# 20180608-iot.net
KiCad netlist of a schematic drawn in EAGLE
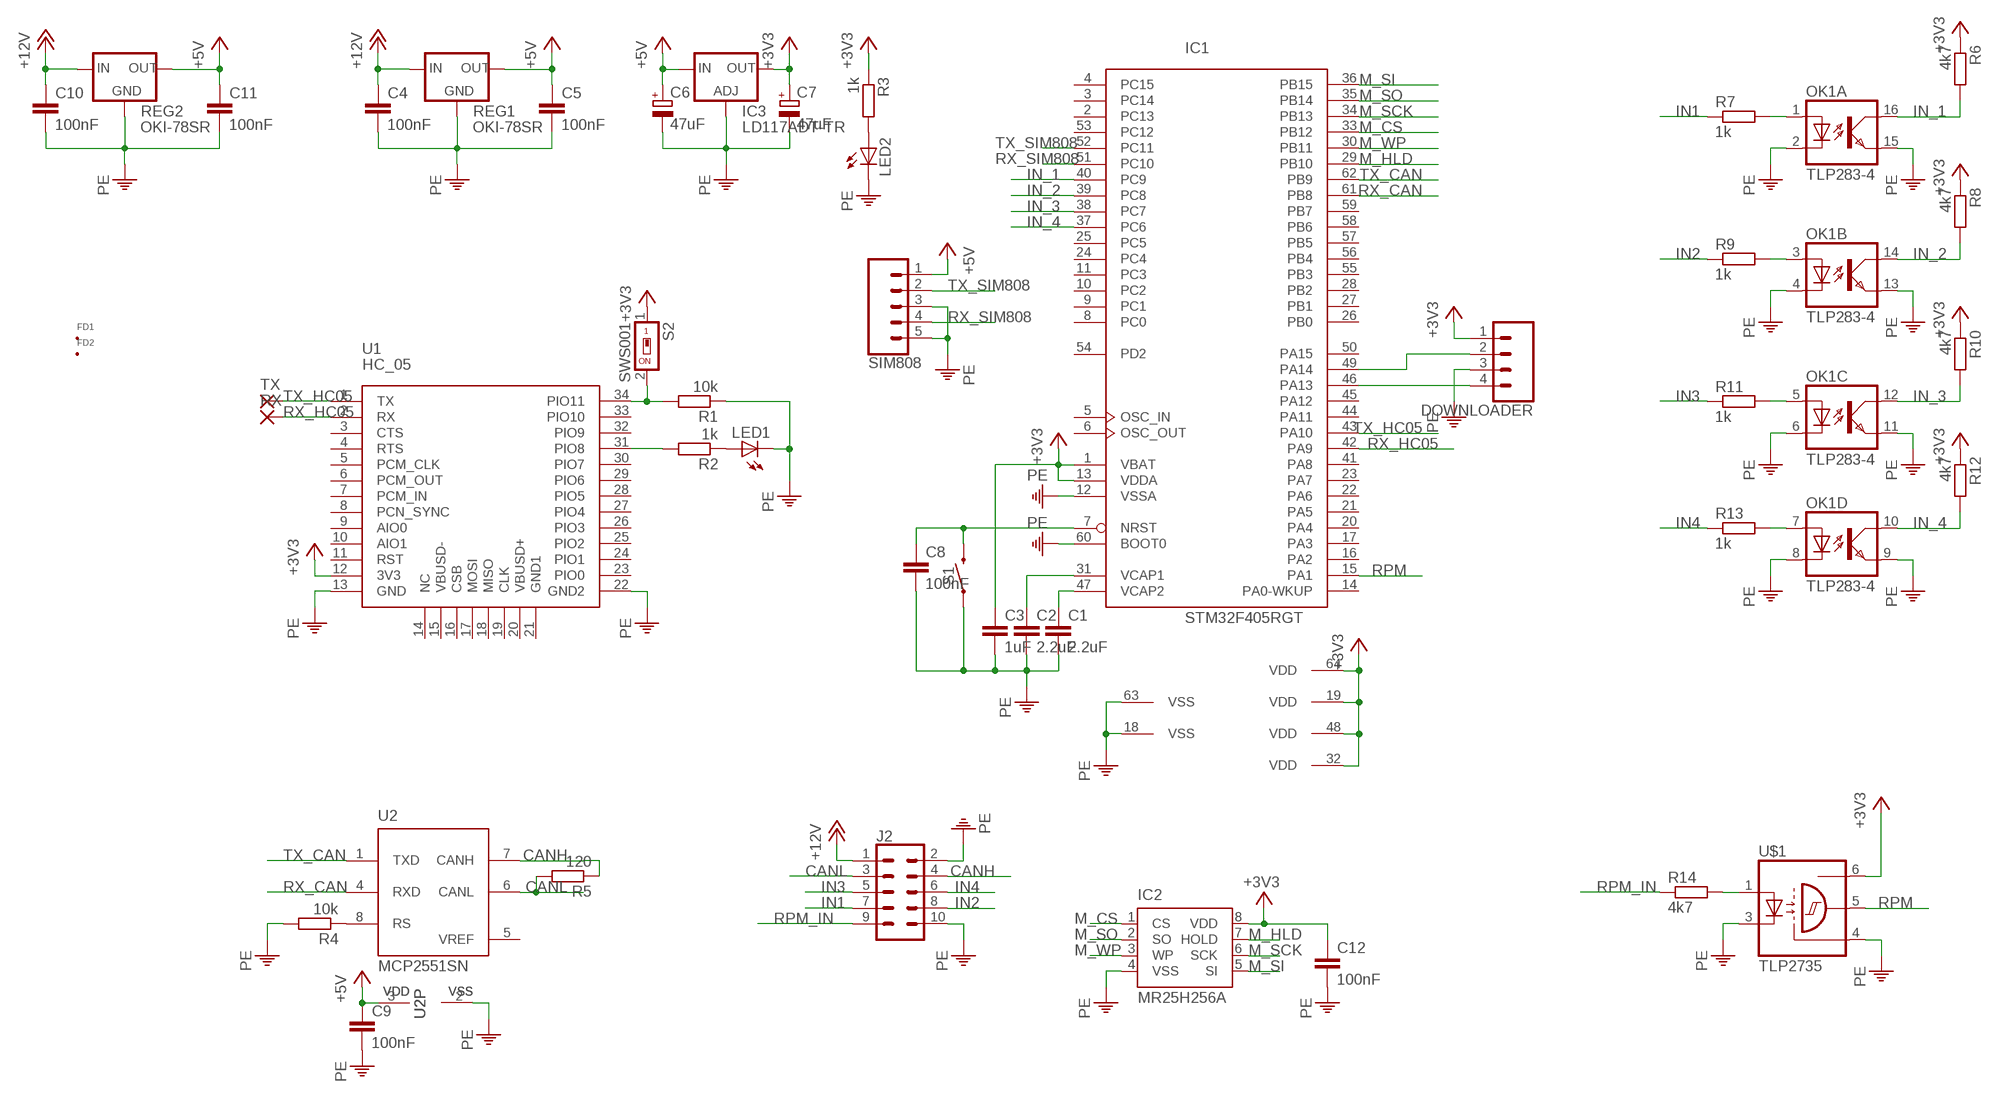
[diagram p0: schematic, sheet 1]

(export (version "E")
  (design (tool "Eeschema 10.0.6"))
  (components
    (comp (ref "C1")
      (value "2.2uF")
      (footprint "eagle-import:C0805")
      (libsource (lib "eagle-import") (part "C-EUC0805"))
    )
    (comp (ref "C2")
      (value "2.2uF")
      (footprint "eagle-import:C0805")
      (libsource (lib "eagle-import") (part "C-EUC0805"))
    )
    (comp (ref "C3")
      (value "1uF")
      (footprint "eagle-import:C0805")
      (libsource (lib "eagle-import") (part "C-EUC0805"))
    )
    (comp (ref "C4")
      (value "100nF")
      (footprint "eagle-import:C0805")
      (libsource (lib "eagle-import") (part "C-EUC0805"))
    )
    (comp (ref "C5")
      (value "100nF")
      (footprint "eagle-import:C0805")
      (libsource (lib "eagle-import") (part "C-EUC0805"))
    )
    (comp (ref "C6")
      (value "47uF")
      (footprint "eagle-import:CT7343")
      (libsource (lib "eagle-import") (part "CPOL-EUCT7343"))
    )
    (comp (ref "C7")
      (value "47uF")
      (footprint "eagle-import:CT7343")
      (libsource (lib "eagle-import") (part "CPOL-EUCT7343"))
    )
    (comp (ref "C8")
      (value "100nF")
      (footprint "eagle-import:C0805")
      (libsource (lib "eagle-import") (part "C-EUC0805"))
    )
    (comp (ref "C9")
      (value "100nF")
      (footprint "eagle-import:C0805")
      (libsource (lib "eagle-import") (part "C-EUC0805"))
    )
    (comp (ref "C10")
      (value "100nF")
      (footprint "eagle-import:C0805")
      (libsource (lib "eagle-import") (part "C-EUC0805"))
    )
    (comp (ref "C11")
      (value "100nF")
      (footprint "eagle-import:C0805")
      (libsource (lib "eagle-import") (part "C-EUC0805"))
    )
    (comp (ref "C12")
      (value "100nF")
      (footprint "eagle-import:C0805")
      (libsource (lib "eagle-import") (part "C-EUC0805"))
    )
    (comp (ref "DOWNLOADER")
      (value "CONN_04")
      (footprint "eagle-import:1X04")
      (libsource (lib "eagle-import") (part "CONN_04"))
    )
    (comp (ref "FD1")
      (value "FID_40MIL")
      (footprint "eagle-import:FID_040")
      (libsource (lib "eagle-import") (part "FID_40MIL"))
    )
    (comp (ref "FD2")
      (value "FID_40MIL")
      (footprint "eagle-import:FID_040")
      (libsource (lib "eagle-import") (part "FID_40MIL"))
    )
    (comp (ref "IC1")
      (value "STM32F405RGT")
      (footprint "eagle-import:LQFP64")
      (fields (field (name "SPICEPREFIX") "X"))
      (libsource (lib "eagle-import") (part "STM32F405RTG"))
    )
    (comp (ref "IC2")
      (value "MR25H256A")
      (footprint "eagle-import:SON127P600X500X90-9T210")
      (libsource (lib "eagle-import") (part "MR25H256A"))
    )
    (comp (ref "IC3")
      (value "LD117ADT-TR")
      (footprint "eagle-import:DPACK")
      (libsource (lib "eagle-import") (part "LD117A?DT-TR"))
    )
    (comp (ref "J2")
      (value "CONN_05X2")
      (footprint "eagle-import:2X5-EDGE_SMD")
      (libsource (lib "eagle-import") (part "CONN_05X2"))
    )
    (comp (ref "LED1")
      (value "LEDCHIP-LED0805")
      (footprint "eagle-import:CHIP-LED0805")
      (libsource (lib "eagle-import") (part "LEDCHIP-LED0805"))
    )
    (comp (ref "LED2")
      (value "LEDCHIP-LED0805")
      (footprint "eagle-import:CHIP-LED0805")
      (libsource (lib "eagle-import") (part "LEDCHIP-LED0805"))
    )
    (comp (ref "OK1")
      (value "TLP283-4")
      (footprint "eagle-import:MINI-FLAT-16")
      (libsource (lib "eagle-import") (part "TLP283-4"))
    )
    (comp (ref "R1")
      (value "10k")
      (footprint "eagle-import:R0805")
      (libsource (lib "eagle-import") (part "R-EU_R0805"))
    )
    (comp (ref "R2")
      (value "1k")
      (footprint "eagle-import:R0805")
      (libsource (lib "eagle-import") (part "R-EU_R0805"))
    )
    (comp (ref "R3")
      (value "1k")
      (footprint "eagle-import:R0805")
      (libsource (lib "eagle-import") (part "R-EU_R0805"))
    )
    (comp (ref "R4")
      (value "10k")
      (footprint "eagle-import:R0805")
      (libsource (lib "eagle-import") (part "R-EU_R0805"))
    )
    (comp (ref "R5")
      (value "120")
      (footprint "eagle-import:R0805")
      (libsource (lib "eagle-import") (part "R-EU_R0805"))
    )
    (comp (ref "R6")
      (value "4k7")
      (footprint "eagle-import:R0805")
      (libsource (lib "eagle-import") (part "R-EU_R0805"))
    )
    (comp (ref "R7")
      (value "1k")
      (footprint "eagle-import:R0805")
      (libsource (lib "eagle-import") (part "R-EU_R0805"))
    )
    (comp (ref "R8")
      (value "4k7")
      (footprint "eagle-import:R0805")
      (libsource (lib "eagle-import") (part "R-EU_R0805"))
    )
    (comp (ref "R9")
      (value "1k")
      (footprint "eagle-import:R0805")
      (libsource (lib "eagle-import") (part "R-EU_R0805"))
    )
    (comp (ref "R10")
      (value "4k7")
      (footprint "eagle-import:R0805")
      (libsource (lib "eagle-import") (part "R-EU_R0805"))
    )
    (comp (ref "R11")
      (value "1k")
      (footprint "eagle-import:R0805")
      (libsource (lib "eagle-import") (part "R-EU_R0805"))
    )
    (comp (ref "R12")
      (value "4k7")
      (footprint "eagle-import:R0805")
      (libsource (lib "eagle-import") (part "R-EU_R0805"))
    )
    (comp (ref "R13")
      (value "1k")
      (footprint "eagle-import:R0805")
      (libsource (lib "eagle-import") (part "R-EU_R0805"))
    )
    (comp (ref "R14")
      (value "4k7")
      (footprint "eagle-import:R0805")
      (libsource (lib "eagle-import") (part "R-EU_R0805"))
    )
    (comp (ref "REG1")
      (value "OKI-78SR")
      (footprint "eagle-import:HDRV3W64P254_1X3_1195X508X838B")
      (libsource (lib "eagle-import") (part "OKI-78SR"))
    )
    (comp (ref "REG2")
      (value "OKI-78SR")
      (footprint "eagle-import:HDRV3W64P254_1X3_1195X508X838B")
      (libsource (lib "eagle-import") (part "OKI-78SR"))
    )
    (comp (ref "RX")
      (value "SMD2")
      (footprint "eagle-import:SMD1,27-2,54")
      (libsource (lib "eagle-import") (part "SMD2"))
    )
    (comp (ref "S1")
      (value "MOMENTARY-SWITCH-SPST-SMD-6.0X3.5MM")
      (footprint "eagle-import:TACTILE_SWITCH_SMD_6.0X3.5MM")
      (libsource (lib "eagle-import") (part "MOMENTARY-SWITCH-SPST-SMD-6.0X3.5MM"))
    )
    (comp (ref "S2")
      (value "SWS001")
      (footprint "eagle-import:SMS-001")
      (libsource (lib "eagle-import") (part "SWS001"))
    )
    (comp (ref "SIM808")
      (value "CONN_05")
      (footprint "eagle-import:1X05")
      (libsource (lib "eagle-import") (part "CONN_05"))
    )
    (comp (ref "TX")
      (value "SMD2")
      (footprint "eagle-import:SMD1,27-2,54")
      (libsource (lib "eagle-import") (part "SMD2"))
    )
    (comp (ref "U$1")
      (value "TLP2735")
      (footprint "eagle-import:SOIC127P1000X210-6")
      (libsource (lib "eagle-import") (part "TLP2735"))
    )
    (comp (ref "U1")
      (value "HC_05")
      (footprint "eagle-import:BLUETOOTH_SMD")
      (libsource (lib "eagle-import") (part "HC_05"))
    )
    (comp (ref "U2")
      (value "MCP2551SN")
      (footprint "eagle-import:SO-08")
      (fields (field (name "SPICEPREFIX") "X"))
      (libsource (lib "eagle-import") (part "MCP2551SN"))
    )
  )
  (nets
    (net (code "1") (name "+3V3") (class "Default")
      (node (ref "C12") (pin "1") (pinfunction "1_1") (pintype "passive"))
      (node (ref "C3") (pin "1") (pinfunction "1_1") (pintype "passive"))
      (node (ref "C7") (pin "+") (pinfunction "+_+") (pintype "passive"))
      (node (ref "DOWNLOADER") (pin "1") (pinfunction "1_1") (pintype "passive"))
      (node (ref "IC1") (pin "1") (pinfunction "VBAT_1") (pintype "power_in"))
      (node (ref "IC1") (pin "13") (pinfunction "VDDA_13") (pintype "power_in"))
      (node (ref "IC1") (pin "19") (pinfunction "VDD_19") (pintype "power_in"))
      (node (ref "IC1") (pin "32") (pinfunction "VDD_32") (pintype "power_in"))
      (node (ref "IC1") (pin "48") (pinfunction "VDD_48") (pintype "power_in"))
      (node (ref "IC1") (pin "64") (pinfunction "VDD_64") (pintype "power_in"))
      (node (ref "IC2") (pin "8") (pinfunction "VDD_8") (pintype "power_in"))
      (node (ref "IC3") (pin "4") (pinfunction "OUT_4") (pintype "passive"))
      (node (ref "R10") (pin "1") (pinfunction "1_1") (pintype "passive"))
      (node (ref "R12") (pin "1") (pinfunction "1_1") (pintype "passive"))
      (node (ref "R3") (pin "1") (pinfunction "1_1") (pintype "passive"))
      (node (ref "R6") (pin "1") (pinfunction "1_1") (pintype "passive"))
      (node (ref "R8") (pin "1") (pinfunction "1_1") (pintype "passive"))
      (node (ref "S2") (pin "1") (pinfunction "1_1") (pintype "passive"))
      (node (ref "U$1") (pin "6") (pinfunction "VCC_6") (pintype "passive"))
      (node (ref "U1") (pin "12") (pinfunction "3V3_12") (pintype "bidirectional"))
    )
    (net (code "2") (name "+5V") (class "Default")
      (node (ref "C11") (pin "1") (pinfunction "1_1") (pintype "passive"))
      (node (ref "C5") (pin "1") (pinfunction "1_1") (pintype "passive"))
      (node (ref "C6") (pin "+") (pinfunction "+_+") (pintype "passive"))
      (node (ref "C9") (pin "1") (pinfunction "1_1") (pintype "passive"))
      (node (ref "IC3") (pin "3") (pinfunction "IN_3") (pintype "input"))
      (node (ref "REG1") (pin "3") (pinfunction "OUT_3") (pintype "passive"))
      (node (ref "REG2") (pin "3") (pinfunction "OUT_3") (pintype "passive"))
      (node (ref "SIM808") (pin "1") (pinfunction "1_1") (pintype "passive"))
      (node (ref "U2") (pin "3") (pinfunction "VDD_3") (pintype "power_in"))
    )
    (net (code "3") (name "+12V") (class "Default")
      (node (ref "C10") (pin "1") (pinfunction "1_1") (pintype "passive"))
      (node (ref "C4") (pin "1") (pinfunction "1_1") (pintype "passive"))
      (node (ref "J2") (pin "1") (pinfunction "1_1") (pintype "passive"))
      (node (ref "REG1") (pin "1") (pinfunction "IN_1") (pintype "input"))
      (node (ref "REG2") (pin "1") (pinfunction "IN_1") (pintype "input"))
    )
    (net (code "4") (name "/CANH") (class "Default")
      (node (ref "J2") (pin "4") (pinfunction "4_4") (pintype "passive"))
      (node (ref "R5") (pin "1") (pinfunction "1_1") (pintype "passive"))
      (node (ref "U2") (pin "7") (pinfunction "CANH_7") (pintype "bidirectional"))
    )
    (net (code "5") (name "/CANL") (class "Default")
      (node (ref "J2") (pin "3") (pinfunction "3_3") (pintype "passive"))
      (node (ref "R5") (pin "2") (pinfunction "2_2") (pintype "passive"))
      (node (ref "U2") (pin "6") (pinfunction "CANL_6") (pintype "bidirectional"))
    )
    (net (code "6") (name "/IN1") (class "Default")
      (node (ref "J2") (pin "7") (pinfunction "7_7") (pintype "passive"))
      (node (ref "R7") (pin "1") (pinfunction "1_1") (pintype "passive"))
    )
    (net (code "7") (name "/IN2") (class "Default")
      (node (ref "J2") (pin "8") (pinfunction "8_8") (pintype "passive"))
      (node (ref "R9") (pin "1") (pinfunction "1_1") (pintype "passive"))
    )
    (net (code "8") (name "/IN3") (class "Default")
      (node (ref "J2") (pin "5") (pinfunction "5_5") (pintype "passive"))
      (node (ref "R11") (pin "1") (pinfunction "1_1") (pintype "passive"))
    )
    (net (code "9") (name "/IN4") (class "Default")
      (node (ref "J2") (pin "6") (pinfunction "6_6") (pintype "passive"))
      (node (ref "R13") (pin "1") (pinfunction "1_1") (pintype "passive"))
    )
    (net (code "10") (name "/IN_1") (class "Default")
      (node (ref "IC1") (pin "40") (pinfunction "PC9_40") (pintype "bidirectional"))
      (node (ref "OK1") (pin "16") (pinfunction "COL_16") (pintype "passive"))
      (node (ref "R6") (pin "2") (pinfunction "2_2") (pintype "passive"))
    )
    (net (code "11") (name "/IN_2") (class "Default")
      (node (ref "IC1") (pin "39") (pinfunction "PC8_39") (pintype "bidirectional"))
      (node (ref "OK1") (pin "14") (pinfunction "COL_14") (pintype "passive"))
      (node (ref "R8") (pin "2") (pinfunction "2_2") (pintype "passive"))
    )
    (net (code "12") (name "/IN_3") (class "Default")
      (node (ref "IC1") (pin "38") (pinfunction "PC7_38") (pintype "bidirectional"))
      (node (ref "OK1") (pin "12") (pinfunction "COL_12") (pintype "passive"))
      (node (ref "R10") (pin "2") (pinfunction "2_2") (pintype "passive"))
    )
    (net (code "13") (name "/IN_4") (class "Default")
      (node (ref "IC1") (pin "37") (pinfunction "PC6_37") (pintype "bidirectional"))
      (node (ref "OK1") (pin "10") (pinfunction "COL_10") (pintype "passive"))
      (node (ref "R12") (pin "2") (pinfunction "2_2") (pintype "passive"))
    )
    (net (code "14") (name "/M_CS") (class "Default")
      (node (ref "IC1") (pin "33") (pinfunction "PB12_33") (pintype "bidirectional"))
      (node (ref "IC2") (pin "1") (pinfunction "CS_1") (pintype "bidirectional"))
    )
    (net (code "15") (name "/M_HLD") (class "Default")
      (node (ref "IC1") (pin "29") (pinfunction "PB10_29") (pintype "bidirectional"))
      (node (ref "IC2") (pin "7") (pinfunction "HOLD_7") (pintype "output"))
    )
    (net (code "16") (name "/M_SCK") (class "Default")
      (node (ref "IC1") (pin "34") (pinfunction "PB13_34") (pintype "bidirectional"))
      (node (ref "IC2") (pin "6") (pinfunction "SCK_6") (pintype "power_in"))
    )
    (net (code "17") (name "/M_SI") (class "Default")
      (node (ref "IC1") (pin "36") (pinfunction "PB15_36") (pintype "bidirectional"))
      (node (ref "IC2") (pin "5") (pinfunction "SI_5") (pintype "input"))
    )
    (net (code "18") (name "/M_SO") (class "Default")
      (node (ref "IC1") (pin "35") (pinfunction "PB14_35") (pintype "bidirectional"))
      (node (ref "IC2") (pin "2") (pinfunction "SO_2") (pintype "input"))
    )
    (net (code "19") (name "/M_WP") (class "Default")
      (node (ref "IC1") (pin "30") (pinfunction "PB11_30") (pintype "bidirectional"))
      (node (ref "IC2") (pin "3") (pinfunction "WP_3") (pintype "input"))
    )
    (net (code "20") (name "/RPM") (class "Default")
      (node (ref "IC1") (pin "15") (pinfunction "PA1_15") (pintype "bidirectional"))
      (node (ref "U$1") (pin "5") (pinfunction "OUT_5") (pintype "passive"))
    )
    (net (code "21") (name "/RPM_IN") (class "Default")
      (node (ref "J2") (pin "9") (pinfunction "9_9") (pintype "passive"))
      (node (ref "R14") (pin "1") (pinfunction "1_1") (pintype "passive"))
    )
    (net (code "22") (name "/RX_CAN") (class "Default")
      (node (ref "IC1") (pin "61") (pinfunction "PB8_61") (pintype "bidirectional"))
      (node (ref "U2") (pin "4") (pinfunction "RXD_4") (pintype "output"))
    )
    (net (code "23") (name "/RX_HC05") (class "Default")
      (node (ref "IC1") (pin "42") (pinfunction "PA9_42") (pintype "bidirectional"))
      (node (ref "RX") (pin "1") (pinfunction "P_1") (pintype "passive"))
      (node (ref "U1") (pin "2") (pinfunction "RX_2") (pintype "bidirectional"))
    )
    (net (code "24") (name "/RX_SIM808") (class "Default")
      (node (ref "IC1") (pin "51") (pinfunction "PC10_51") (pintype "bidirectional"))
      (node (ref "SIM808") (pin "4") (pinfunction "4_4") (pintype "passive"))
    )
    (net (code "25") (name "/TX_CAN") (class "Default")
      (node (ref "IC1") (pin "62") (pinfunction "PB9_62") (pintype "bidirectional"))
      (node (ref "U2") (pin "1") (pinfunction "TXD_1") (pintype "input"))
    )
    (net (code "26") (name "/TX_HC05") (class "Default")
      (node (ref "IC1") (pin "43") (pinfunction "PA10_43") (pintype "bidirectional"))
      (node (ref "TX") (pin "1") (pinfunction "P_1") (pintype "passive"))
      (node (ref "U1") (pin "1") (pinfunction "TX_1") (pintype "bidirectional"))
    )
    (net (code "27") (name "/TX_SIM808") (class "Default")
      (node (ref "IC1") (pin "52") (pinfunction "PC11_52") (pintype "bidirectional"))
      (node (ref "SIM808") (pin "2") (pinfunction "2_2") (pintype "passive"))
    )
    (net (code "28") (name "/VREF") (class "Default")
      (node (ref "U2") (pin "5") (pinfunction "VREF_5") (pintype "power_in"))
    )
    (net (code "29") (name "Net-(IC1A-NRST)") (class "Default")
      (node (ref "C8") (pin "1") (pinfunction "1_1") (pintype "passive"))
      (node (ref "IC1") (pin "7") (pinfunction "NRST_7") (pintype "bidirectional"))
      (node (ref "S1") (pin "2") (pinfunction "2_2") (pintype "passive"))
    )
    (net (code "30") (name "Net-(IC1A-PA13)") (class "Default")
      (node (ref "DOWNLOADER") (pin "4") (pinfunction "4_4") (pintype "passive"))
      (node (ref "IC1") (pin "46") (pinfunction "PA13_46") (pintype "bidirectional"))
    )
    (net (code "31") (name "Net-(IC1A-PA14)") (class "Default")
      (node (ref "DOWNLOADER") (pin "2") (pinfunction "2_2") (pintype "passive"))
      (node (ref "IC1") (pin "49") (pinfunction "PA14_49") (pintype "bidirectional"))
    )
    (net (code "32") (name "Net-(IC1A-VCAP1)") (class "Default")
      (node (ref "C2") (pin "1") (pinfunction "1_1") (pintype "passive"))
      (node (ref "IC1") (pin "31") (pinfunction "VCAP1_31") (pintype "power_in"))
    )
    (net (code "33") (name "Net-(IC1A-VCAP2)") (class "Default")
      (node (ref "C1") (pin "1") (pinfunction "1_1") (pintype "passive"))
      (node (ref "IC1") (pin "47") (pinfunction "VCAP2_47") (pintype "power_in"))
    )
    (net (code "34") (name "Net-(LED1-PadA)") (class "Default")
      (node (ref "LED1") (pin "A") (pinfunction "A_A") (pintype "passive"))
      (node (ref "R2") (pin "1") (pinfunction "1_1") (pintype "passive"))
    )
    (net (code "35") (name "Net-(LED2-PadA)") (class "Default")
      (node (ref "LED2") (pin "A") (pinfunction "A_A") (pintype "passive"))
      (node (ref "R3") (pin "2") (pinfunction "2_2") (pintype "passive"))
    )
    (net (code "36") (name "Net-(OK1A-A)") (class "Default")
      (node (ref "OK1") (pin "1") (pinfunction "A_1") (pintype "passive"))
      (node (ref "R7") (pin "2") (pinfunction "2_2") (pintype "passive"))
    )
    (net (code "37") (name "Net-(OK1B-A)") (class "Default")
      (node (ref "OK1") (pin "3") (pinfunction "A_3") (pintype "passive"))
      (node (ref "R9") (pin "2") (pinfunction "2_2") (pintype "passive"))
    )
    (net (code "38") (name "Net-(OK1C-A)") (class "Default")
      (node (ref "OK1") (pin "5") (pinfunction "A_5") (pintype "passive"))
      (node (ref "R11") (pin "2") (pinfunction "2_2") (pintype "passive"))
    )
    (net (code "39") (name "Net-(OK1D-A)") (class "Default")
      (node (ref "OK1") (pin "7") (pinfunction "A_7") (pintype "passive"))
      (node (ref "R13") (pin "2") (pinfunction "2_2") (pintype "passive"))
    )
    (net (code "40") (name "Net-(U$1-A)") (class "Default")
      (node (ref "R14") (pin "2") (pinfunction "2_2") (pintype "passive"))
      (node (ref "U$1") (pin "1") (pinfunction "A_1") (pintype "passive"))
    )
    (net (code "41") (name "Net-(U1-PIO8)") (class "Default")
      (node (ref "R2") (pin "2") (pinfunction "2_2") (pintype "passive"))
      (node (ref "U1") (pin "31") (pinfunction "PIO8_31") (pintype "bidirectional"))
    )
    (net (code "42") (name "Net-(U1-PIO11)") (class "Default")
      (node (ref "R1") (pin "2") (pinfunction "2_2") (pintype "passive"))
      (node (ref "S2") (pin "2") (pinfunction "2_2") (pintype "passive"))
      (node (ref "U1") (pin "34") (pinfunction "PIO11_34") (pintype "bidirectional"))
    )
    (net (code "43") (name "Net-(U2A-RS)") (class "Default")
      (node (ref "R4") (pin "1") (pinfunction "1_1") (pintype "passive"))
      (node (ref "U2") (pin "8") (pinfunction "RS_8") (pintype "input"))
    )
    (net (code "44") (name "PE") (class "Default")
      (node (ref "C1") (pin "2") (pinfunction "2_2") (pintype "passive"))
      (node (ref "C10") (pin "2") (pinfunction "2_2") (pintype "passive"))
      (node (ref "C11") (pin "2") (pinfunction "2_2") (pintype "passive"))
      (node (ref "C12") (pin "2") (pinfunction "2_2") (pintype "passive"))
      (node (ref "C2") (pin "2") (pinfunction "2_2") (pintype "passive"))
      (node (ref "C3") (pin "2") (pinfunction "2_2") (pintype "passive"))
      (node (ref "C4") (pin "2") (pinfunction "2_2") (pintype "passive"))
      (node (ref "C5") (pin "2") (pinfunction "2_2") (pintype "passive"))
      (node (ref "C6") (pin "-") (pinfunction "-_-") (pintype "passive"))
      (node (ref "C7") (pin "-") (pinfunction "-_-") (pintype "passive"))
      (node (ref "C8") (pin "2") (pinfunction "2_2") (pintype "passive"))
      (node (ref "C9") (pin "2") (pinfunction "2_2") (pintype "passive"))
      (node (ref "DOWNLOADER") (pin "3") (pinfunction "3_3") (pintype "passive"))
      (node (ref "IC1") (pin "12") (pinfunction "VSSA_12") (pintype "power_in"))
      (node (ref "IC1") (pin "18") (pinfunction "VSS_18") (pintype "power_in"))
      (node (ref "IC1") (pin "60") (pinfunction "BOOT0_60") (pintype "input"))
      (node (ref "IC1") (pin "63") (pinfunction "VSS_63") (pintype "power_in"))
      (node (ref "IC2") (pin "4") (pinfunction "VSS_4") (pintype "input"))
      (node (ref "IC3") (pin "1") (pinfunction "ADJ_1") (pintype "input"))
      (node (ref "J2") (pin "10") (pinfunction "10_10") (pintype "passive"))
      (node (ref "J2") (pin "2") (pinfunction "2_2") (pintype "passive"))
      (node (ref "LED1") (pin "C") (pinfunction "C_C") (pintype "passive"))
      (node (ref "LED2") (pin "C") (pinfunction "C_C") (pintype "passive"))
      (node (ref "OK1") (pin "11") (pinfunction "EMIT_11") (pintype "passive"))
      (node (ref "OK1") (pin "13") (pinfunction "EMIT_13") (pintype "passive"))
      (node (ref "OK1") (pin "15") (pinfunction "EMIT_15") (pintype "passive"))
      (node (ref "OK1") (pin "2") (pinfunction "C_2") (pintype "passive"))
      (node (ref "OK1") (pin "4") (pinfunction "C_4") (pintype "passive"))
      (node (ref "OK1") (pin "6") (pinfunction "C_6") (pintype "passive"))
      (node (ref "OK1") (pin "8") (pinfunction "C_8") (pintype "passive"))
      (node (ref "OK1") (pin "9") (pinfunction "EMIT_9") (pintype "passive"))
      (node (ref "R1") (pin "1") (pinfunction "1_1") (pintype "passive"))
      (node (ref "R4") (pin "2") (pinfunction "2_2") (pintype "passive"))
      (node (ref "REG1") (pin "2") (pinfunction "GND_2") (pintype "input"))
      (node (ref "REG2") (pin "2") (pinfunction "GND_2") (pintype "input"))
      (node (ref "S1") (pin "1") (pinfunction "1_1") (pintype "passive"))
      (node (ref "SIM808") (pin "3") (pinfunction "3_3") (pintype "passive"))
      (node (ref "SIM808") (pin "5") (pinfunction "5_5") (pintype "passive"))
      (node (ref "U$1") (pin "3") (pinfunction "C_3") (pintype "passive"))
      (node (ref "U$1") (pin "4") (pinfunction "GND_4") (pintype "passive"))
      (node (ref "U1") (pin "13") (pinfunction "GND_13") (pintype "bidirectional"))
      (node (ref "U1") (pin "22") (pinfunction "GND2_22") (pintype "bidirectional"))
      (node (ref "U2") (pin "2") (pinfunction "VSS_2") (pintype "power_in"))
    )
    (net (code "45") (name "unconnected-(IC1A-OSC_IN-Pad5)") (class "Default")
      (node (ref "IC1") (pin "5") (pinfunction "OSC_IN_5") (pintype "bidirectional"))
    )
    (net (code "46") (name "unconnected-(IC1A-OSC_OUT-Pad6)") (class "Default")
      (node (ref "IC1") (pin "6") (pinfunction "OSC_OUT_6") (pintype "bidirectional"))
    )
    (net (code "47") (name "unconnected-(IC1A-PA0-WKUP-Pad14)") (class "Default")
      (node (ref "IC1") (pin "14") (pinfunction "PA0-WKUP_14") (pintype "bidirectional"))
    )
    (net (code "48") (name "unconnected-(IC1A-PA2-Pad16)") (class "Default")
      (node (ref "IC1") (pin "16") (pinfunction "PA2_16") (pintype "bidirectional"))
    )
    (net (code "49") (name "unconnected-(IC1A-PA3-Pad17)") (class "Default")
      (node (ref "IC1") (pin "17") (pinfunction "PA3_17") (pintype "bidirectional"))
    )
    (net (code "50") (name "unconnected-(IC1A-PA4-Pad20)") (class "Default")
      (node (ref "IC1") (pin "20") (pinfunction "PA4_20") (pintype "bidirectional"))
    )
    (net (code "51") (name "unconnected-(IC1A-PA5-Pad21)") (class "Default")
      (node (ref "IC1") (pin "21") (pinfunction "PA5_21") (pintype "bidirectional"))
    )
    (net (code "52") (name "unconnected-(IC1A-PA6-Pad22)") (class "Default")
      (node (ref "IC1") (pin "22") (pinfunction "PA6_22") (pintype "bidirectional"))
    )
    (net (code "53") (name "unconnected-(IC1A-PA7-Pad23)") (class "Default")
      (node (ref "IC1") (pin "23") (pinfunction "PA7_23") (pintype "bidirectional"))
    )
    (net (code "54") (name "unconnected-(IC1A-PA8-Pad41)") (class "Default")
      (node (ref "IC1") (pin "41") (pinfunction "PA8_41") (pintype "bidirectional"))
    )
    (net (code "55") (name "unconnected-(IC1A-PA11-Pad44)") (class "Default")
      (node (ref "IC1") (pin "44") (pinfunction "PA11_44") (pintype "bidirectional"))
    )
    (net (code "56") (name "unconnected-(IC1A-PA12-Pad45)") (class "Default")
      (node (ref "IC1") (pin "45") (pinfunction "PA12_45") (pintype "bidirectional"))
    )
    (net (code "57") (name "unconnected-(IC1A-PA15-Pad50)") (class "Default")
      (node (ref "IC1") (pin "50") (pinfunction "PA15_50") (pintype "bidirectional"))
    )
    (net (code "58") (name "unconnected-(IC1A-PB0-Pad26)") (class "Default")
      (node (ref "IC1") (pin "26") (pinfunction "PB0_26") (pintype "bidirectional"))
    )
    (net (code "59") (name "unconnected-(IC1A-PB1-Pad27)") (class "Default")
      (node (ref "IC1") (pin "27") (pinfunction "PB1_27") (pintype "bidirectional"))
    )
    (net (code "60") (name "unconnected-(IC1A-PB2-Pad28)") (class "Default")
      (node (ref "IC1") (pin "28") (pinfunction "PB2_28") (pintype "bidirectional"))
    )
    (net (code "61") (name "unconnected-(IC1A-PB3-Pad55)") (class "Default")
      (node (ref "IC1") (pin "55") (pinfunction "PB3_55") (pintype "bidirectional"))
    )
    (net (code "62") (name "unconnected-(IC1A-PB4-Pad56)") (class "Default")
      (node (ref "IC1") (pin "56") (pinfunction "PB4_56") (pintype "bidirectional"))
    )
    (net (code "63") (name "unconnected-(IC1A-PB5-Pad57)") (class "Default")
      (node (ref "IC1") (pin "57") (pinfunction "PB5_57") (pintype "bidirectional"))
    )
    (net (code "64") (name "unconnected-(IC1A-PB6-Pad58)") (class "Default")
      (node (ref "IC1") (pin "58") (pinfunction "PB6_58") (pintype "bidirectional"))
    )
    (net (code "65") (name "unconnected-(IC1A-PB7-Pad59)") (class "Default")
      (node (ref "IC1") (pin "59") (pinfunction "PB7_59") (pintype "bidirectional"))
    )
    (net (code "66") (name "unconnected-(IC1A-PC0-Pad8)") (class "Default")
      (node (ref "IC1") (pin "8") (pinfunction "PC0_8") (pintype "bidirectional"))
    )
    (net (code "67") (name "unconnected-(IC1A-PC1-Pad9)") (class "Default")
      (node (ref "IC1") (pin "9") (pinfunction "PC1_9") (pintype "bidirectional"))
    )
    (net (code "68") (name "unconnected-(IC1A-PC2-Pad10)") (class "Default")
      (node (ref "IC1") (pin "10") (pinfunction "PC2_10") (pintype "bidirectional"))
    )
    (net (code "69") (name "unconnected-(IC1A-PC3-Pad11)") (class "Default")
      (node (ref "IC1") (pin "11") (pinfunction "PC3_11") (pintype "bidirectional"))
    )
    (net (code "70") (name "unconnected-(IC1A-PC4-Pad24)") (class "Default")
      (node (ref "IC1") (pin "24") (pinfunction "PC4_24") (pintype "bidirectional"))
    )
    (net (code "71") (name "unconnected-(IC1A-PC5-Pad25)") (class "Default")
      (node (ref "IC1") (pin "25") (pinfunction "PC5_25") (pintype "bidirectional"))
    )
    (net (code "72") (name "unconnected-(IC1A-PC12-Pad53)") (class "Default")
      (node (ref "IC1") (pin "53") (pinfunction "PC12_53") (pintype "bidirectional"))
    )
    (net (code "73") (name "unconnected-(IC1A-PC13-Pad2)") (class "Default")
      (node (ref "IC1") (pin "2") (pinfunction "PC13_2") (pintype "bidirectional"))
    )
    (net (code "74") (name "unconnected-(IC1A-PC14-Pad3)") (class "Default")
      (node (ref "IC1") (pin "3") (pinfunction "PC14_3") (pintype "bidirectional"))
    )
    (net (code "75") (name "unconnected-(IC1A-PC15-Pad4)") (class "Default")
      (node (ref "IC1") (pin "4") (pinfunction "PC15_4") (pintype "bidirectional"))
    )
    (net (code "76") (name "unconnected-(IC1A-PD2-Pad54)") (class "Default")
      (node (ref "IC1") (pin "54") (pinfunction "PD2_54") (pintype "bidirectional"))
    )
    (net (code "77") (name "unconnected-(U1-AIO0-Pad9)") (class "Default")
      (node (ref "U1") (pin "9") (pinfunction "AIO0_9") (pintype "bidirectional"))
    )
    (net (code "78") (name "unconnected-(U1-AIO1-Pad10)") (class "Default")
      (node (ref "U1") (pin "10") (pinfunction "AIO1_10") (pintype "bidirectional"))
    )
    (net (code "79") (name "unconnected-(U1-CLK-Pad19)") (class "Default")
      (node (ref "U1") (pin "19") (pinfunction "CLK_19") (pintype "bidirectional"))
    )
    (net (code "80") (name "unconnected-(U1-CSB-Pad16)") (class "Default")
      (node (ref "U1") (pin "16") (pinfunction "CSB_16") (pintype "bidirectional"))
    )
    (net (code "81") (name "unconnected-(U1-CTS-Pad3)") (class "Default")
      (node (ref "U1") (pin "3") (pinfunction "CTS_3") (pintype "bidirectional"))
    )
    (net (code "82") (name "unconnected-(U1-GND1-Pad21)") (class "Default")
      (node (ref "U1") (pin "21") (pinfunction "GND1_21") (pintype "bidirectional"))
    )
    (net (code "83") (name "unconnected-(U1-MISO-Pad18)") (class "Default")
      (node (ref "U1") (pin "18") (pinfunction "MISO_18") (pintype "bidirectional"))
    )
    (net (code "84") (name "unconnected-(U1-MOSI-Pad17)") (class "Default")
      (node (ref "U1") (pin "17") (pinfunction "MOSI_17") (pintype "bidirectional"))
    )
    (net (code "85") (name "unconnected-(U1-NC-Pad14)") (class "Default")
      (node (ref "U1") (pin "14") (pinfunction "NC_14") (pintype "bidirectional"))
    )
    (net (code "86") (name "unconnected-(U1-PCM_CLK-Pad5)") (class "Default")
      (node (ref "U1") (pin "5") (pinfunction "PCM_CLK_5") (pintype "bidirectional"))
    )
    (net (code "87") (name "unconnected-(U1-PCM_IN-Pad7)") (class "Default")
      (node (ref "U1") (pin "7") (pinfunction "PCM_IN_7") (pintype "bidirectional"))
    )
    (net (code "88") (name "unconnected-(U1-PCM_OUT-Pad6)") (class "Default")
      (node (ref "U1") (pin "6") (pinfunction "PCM_OUT_6") (pintype "bidirectional"))
    )
    (net (code "89") (name "unconnected-(U1-PCN_SYNC-Pad8)") (class "Default")
      (node (ref "U1") (pin "8") (pinfunction "PCN_SYNC_8") (pintype "bidirectional"))
    )
    (net (code "90") (name "unconnected-(U1-PIO0-Pad23)") (class "Default")
      (node (ref "U1") (pin "23") (pinfunction "PIO0_23") (pintype "bidirectional"))
    )
    (net (code "91") (name "unconnected-(U1-PIO1-Pad24)") (class "Default")
      (node (ref "U1") (pin "24") (pinfunction "PIO1_24") (pintype "bidirectional"))
    )
    (net (code "92") (name "unconnected-(U1-PIO2-Pad25)") (class "Default")
      (node (ref "U1") (pin "25") (pinfunction "PIO2_25") (pintype "bidirectional"))
    )
    (net (code "93") (name "unconnected-(U1-PIO3-Pad26)") (class "Default")
      (node (ref "U1") (pin "26") (pinfunction "PIO3_26") (pintype "bidirectional"))
    )
    (net (code "94") (name "unconnected-(U1-PIO4-Pad27)") (class "Default")
      (node (ref "U1") (pin "27") (pinfunction "PIO4_27") (pintype "bidirectional"))
    )
    (net (code "95") (name "unconnected-(U1-PIO5-Pad28)") (class "Default")
      (node (ref "U1") (pin "28") (pinfunction "PIO5_28") (pintype "bidirectional"))
    )
    (net (code "96") (name "unconnected-(U1-PIO6-Pad29)") (class "Default")
      (node (ref "U1") (pin "29") (pinfunction "PIO6_29") (pintype "bidirectional"))
    )
    (net (code "97") (name "unconnected-(U1-PIO7-Pad30)") (class "Default")
      (node (ref "U1") (pin "30") (pinfunction "PIO7_30") (pintype "bidirectional"))
    )
    (net (code "98") (name "unconnected-(U1-PIO9-Pad32)") (class "Default")
      (node (ref "U1") (pin "32") (pinfunction "PIO9_32") (pintype "bidirectional"))
    )
    (net (code "99") (name "unconnected-(U1-PIO10-Pad33)") (class "Default")
      (node (ref "U1") (pin "33") (pinfunction "PIO10_33") (pintype "bidirectional"))
    )
    (net (code "100") (name "unconnected-(U1-RST-Pad11)") (class "Default")
      (node (ref "U1") (pin "11") (pinfunction "RST_11") (pintype "bidirectional"))
    )
    (net (code "101") (name "unconnected-(U1-RTS-Pad4)") (class "Default")
      (node (ref "U1") (pin "4") (pinfunction "RTS_4") (pintype "bidirectional"))
    )
    (net (code "102") (name "unconnected-(U1-VBUSD+-Pad20)") (class "Default")
      (node (ref "U1") (pin "20") (pinfunction "VBUSD+_20") (pintype "bidirectional"))
    )
    (net (code "103") (name "unconnected-(U1-VBUSD--Pad15)") (class "Default")
      (node (ref "U1") (pin "15") (pinfunction "VBUSD-_15") (pintype "bidirectional"))
    )
  )
)
